# 9_h_bridge.net
KiCad netlist of a schematic drawn in Altium Designer
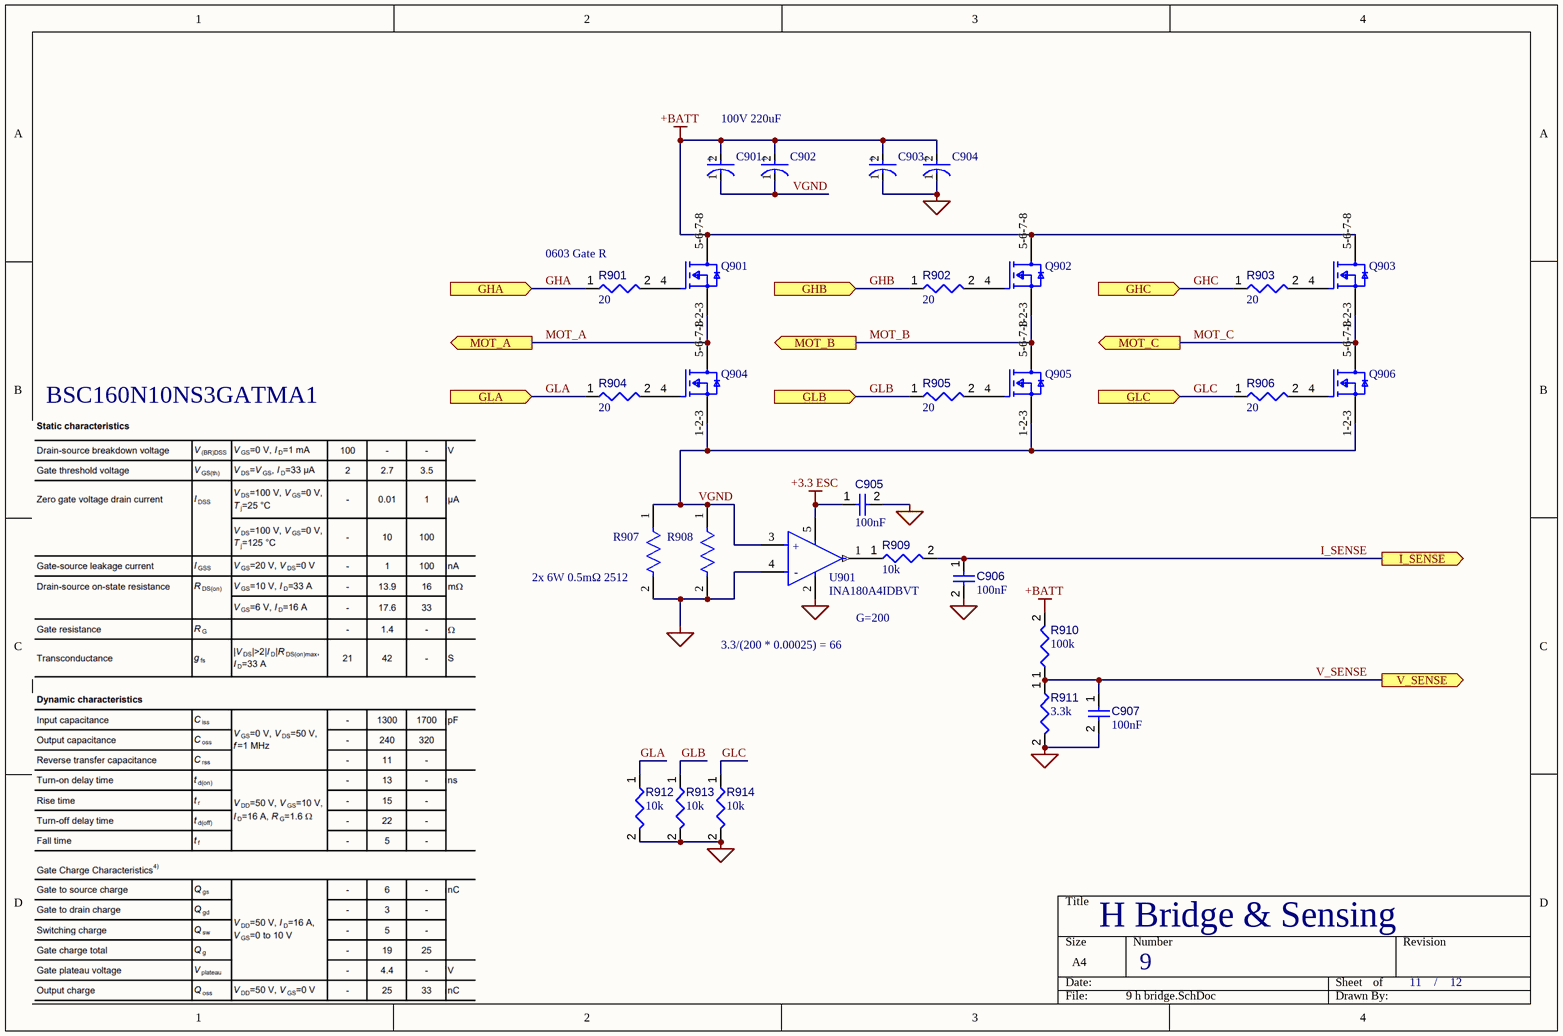
[diagram p0: 9 h bridge.SchDoc]

(export (version "E")
  (design (tool "Eeschema 10.0.6"))
  (components
    (comp (ref "C901")
      (value "EMVY101ARA101MKE0S")
      (footprint "FP-MVYAKE0-MFG")
      (description "CAP ALUM 100UF 20% 100V SMD")
      (fields (field (name "TOLERANCE") "20%"))
      (libsource (lib "Altium Content Vault") (part "203bc49f2ac43e59fd269a8c329ed05"))
    )
    (comp (ref "C902")
      (value "EMVY101ARA101MKE0S")
      (footprint "FP-MVYAKE0-MFG")
      (description "CAP ALUM 100UF 20% 100V SMD")
      (fields (field (name "TOLERANCE") "20%"))
      (libsource (lib "Altium Content Vault") (part "203bc49f2ac43e59fd269a8c329ed05"))
    )
    (comp (ref "C903")
      (value "EMVY101ARA101MKE0S")
      (footprint "FP-MVYAKE0-MFG")
      (description "CAP ALUM 100UF 20% 100V SMD")
      (fields (field (name "TOLERANCE") "20%"))
      (libsource (lib "Altium Content Vault") (part "203bc49f2ac43e59fd269a8c329ed05"))
    )
    (comp (ref "C904")
      (value "EMVY101ARA101MKE0S")
      (footprint "FP-MVYAKE0-MFG")
      (description "CAP ALUM 100UF 20% 100V SMD")
      (fields (field (name "TOLERANCE") "20%"))
      (libsource (lib "Altium Content Vault") (part "203bc49f2ac43e59fd269a8c329ed05"))
    )
    (comp (ref "C905")
      (value "100nF")
      (footprint "CAPC0402(1005)60_L")
      (description "Chip Capacitor, 100nF +/-20%, 25V, 0402, Thickness 0.6 mm")
      (fields (field (name "TOLERANCE") "10%") (field (name "Comment") "Capacitor 100nF +/-20% 25V 0402"))
      (libsource (lib "UBC Uncrewed Aircraft Systems") (part "CAP-NP-2"))
    )
    (comp (ref "C906")
      (value "100nF")
      (footprint "CAPC0402(1005)60_L")
      (description "Chip Capacitor, 100nF +/-20%, 25V, 0402, Thickness 0.6 mm")
      (fields (field (name "TOLERANCE") "10%") (field (name "Comment") "Capacitor 100nF +/-20% 25V 0402"))
      (libsource (lib "UBC Uncrewed Aircraft Systems") (part "CAP-NP-2"))
    )
    (comp (ref "C907")
      (value "100nF")
      (footprint "CAPC0402(1005)60_L")
      (description "Chip Capacitor, 100nF +/-20%, 25V, 0402, Thickness 0.6 mm")
      (fields (field (name "TOLERANCE") "10%") (field (name "Comment") "Capacitor 100nF +/-20% 25V 0402"))
      (libsource (lib "UBC Uncrewed Aircraft Systems") (part "CAP-NP-2"))
    )
    (comp (ref "Q901")
      (value "IAUC120N06S5N017ATMA1")
      (footprint "FP-PG-TDSON-8-MFG")
      (description "MOSFET N-CH 60V 120A TDSON-8-43")
      (libsource (lib "Altium Content Vault") (part "3085234d4498bcd04bc7e5400bb7c96"))
    )
    (comp (ref "Q902")
      (value "IAUC120N06S5N017ATMA1")
      (footprint "FP-PG-TDSON-8-MFG")
      (description "MOSFET N-CH 60V 120A TDSON-8-43")
      (libsource (lib "Altium Content Vault") (part "3085234d4498bcd04bc7e5400bb7c96"))
    )
    (comp (ref "Q903")
      (value "IAUC120N06S5N017ATMA1")
      (footprint "FP-PG-TDSON-8-MFG")
      (description "MOSFET N-CH 60V 120A TDSON-8-43")
      (libsource (lib "Altium Content Vault") (part "3085234d4498bcd04bc7e5400bb7c96"))
    )
    (comp (ref "Q904")
      (value "IAUC120N06S5N017ATMA1")
      (footprint "FP-PG-TDSON-8-MFG")
      (description "MOSFET N-CH 60V 120A TDSON-8-43")
      (libsource (lib "Altium Content Vault") (part "3085234d4498bcd04bc7e5400bb7c96"))
    )
    (comp (ref "Q905")
      (value "IAUC120N06S5N017ATMA1")
      (footprint "FP-PG-TDSON-8-MFG")
      (description "MOSFET N-CH 60V 120A TDSON-8-43")
      (libsource (lib "Altium Content Vault") (part "3085234d4498bcd04bc7e5400bb7c96"))
    )
    (comp (ref "Q906")
      (value "IAUC120N06S5N017ATMA1")
      (footprint "FP-PG-TDSON-8-MFG")
      (description "MOSFET N-CH 60V 120A TDSON-8-43")
      (libsource (lib "Altium Content Vault") (part "3085234d4498bcd04bc7e5400bb7c96"))
    )
    (comp (ref "R901")
      (value "20")
      (footprint "RESC0603(1608)_L")
      (description "Chip Resistor, 20 Ohms, +/-5 %, 0.1 W, -55 to 155 degC, 0603")
      (fields (field (name "TOLERANCE") "5%") (field (name "POWER") "100mW"))
      (libsource (lib "UBC Uncrewed Aircraft Systems") (part "RES-2"))
    )
    (comp (ref "R902")
      (value "20")
      (footprint "RESC0603(1608)_L")
      (description "Chip Resistor, 20 Ohms, +/-5 %, 0.1 W, -55 to 155 degC, 0603")
      (fields (field (name "TOLERANCE") "5%") (field (name "POWER") "100mW"))
      (libsource (lib "UBC Uncrewed Aircraft Systems") (part "RES-2"))
    )
    (comp (ref "R903")
      (value "20")
      (footprint "RESC0603(1608)_L")
      (description "Chip Resistor, 20 Ohms, +/-5 %, 0.1 W, -55 to 155 degC, 0603")
      (fields (field (name "TOLERANCE") "5%") (field (name "POWER") "100mW"))
      (libsource (lib "UBC Uncrewed Aircraft Systems") (part "RES-2"))
    )
    (comp (ref "R904")
      (value "20")
      (footprint "RESC0603(1608)_L")
      (description "Chip Resistor, 20 Ohms, +/-5 %, 0.1 W, -55 to 155 degC, 0603")
      (fields (field (name "TOLERANCE") "5%") (field (name "POWER") "100mW"))
      (libsource (lib "UBC Uncrewed Aircraft Systems") (part "RES-2"))
    )
    (comp (ref "R905")
      (value "20")
      (footprint "RESC0603(1608)_L")
      (description "Chip Resistor, 20 Ohms, +/-5 %, 0.1 W, -55 to 155 degC, 0603")
      (fields (field (name "TOLERANCE") "5%") (field (name "POWER") "100mW"))
      (libsource (lib "UBC Uncrewed Aircraft Systems") (part "RES-2"))
    )
    (comp (ref "R906")
      (value "20")
      (footprint "RESC0603(1608)_L")
      (description "Chip Resistor, 20 Ohms, +/-5 %, 0.1 W, -55 to 155 degC, 0603")
      (fields (field (name "TOLERANCE") "5%") (field (name "POWER") "100mW"))
      (libsource (lib "UBC Uncrewed Aircraft Systems") (part "RES-2"))
    )
    (comp (ref "R907")
      (value "PSL2NTEBL500F")
      (footprint "FP-PSL2NTEBL500F-MFG")
      (description "RES 500 UOHM 1% 8W NONSTANDARD")
      (libsource (lib "Altium Content Vault") (part "1029c3af85768c4190bb7ad29bc67b5"))
    )
    (comp (ref "R908")
      (value "PSL2NTEBL500F")
      (footprint "FP-PSL2NTEBL500F-MFG")
      (description "RES 500 UOHM 1% 8W NONSTANDARD")
      (libsource (lib "Altium Content Vault") (part "1029c3af85768c4190bb7ad29bc67b5"))
    )
    (comp (ref "R909")
      (value "10k")
      (footprint "RESC0402(1005)_L")
      (description "Chip Resistor, 10 kOhms, +/-1 %, 63 mW, -55 to 125 degC, 0402")
      (fields (field (name "POWER") "63mW") (field (name "TOLERANCE") "1%"))
      (libsource (lib "UBC Uncrewed Aircraft Systems") (part "RES-2"))
    )
    (comp (ref "R910")
      (value "100k")
      (footprint "RESC0402(1005)_L")
      (description "Chip Resistor, 100 kOhms, +/-1 %, 63 mW, -55 to 155 degC, 0402")
      (fields (field (name "TOLERANCE") "1%") (field (name "POWER") "63mW"))
      (libsource (lib "UBC Uncrewed Aircraft Systems") (part "RES-2"))
    )
    (comp (ref "R911")
      (value "3.3k")
      (footprint "RESC0402(1005)_L")
      (description "Chip Resistor, 3.3 kOhms, +/-1 %, 63 mW, -55 to 155 degC, 0402")
      (fields (field (name "TOLERANCE") "1%") (field (name "POWER") "63mW"))
      (libsource (lib "UBC Uncrewed Aircraft Systems") (part "RES-2"))
    )
    (comp (ref "R912")
      (value "10k")
      (footprint "RESC0402(1005)_L")
      (description "Chip Resistor, 10 kOhms, +/-1 %, 63 mW, -55 to 125 degC, 0402")
      (fields (field (name "POWER") "63mW") (field (name "TOLERANCE") "1%"))
      (libsource (lib "UBC Uncrewed Aircraft Systems") (part "RES-2"))
    )
    (comp (ref "R913")
      (value "10k")
      (footprint "RESC0402(1005)_L")
      (description "Chip Resistor, 10 kOhms, +/-1 %, 63 mW, -55 to 125 degC, 0402")
      (fields (field (name "POWER") "63mW") (field (name "TOLERANCE") "1%"))
      (libsource (lib "UBC Uncrewed Aircraft Systems") (part "RES-2"))
    )
    (comp (ref "R914")
      (value "10k")
      (footprint "RESC0402(1005)_L")
      (description "Chip Resistor, 10 kOhms, +/-1 %, 63 mW, -55 to 125 degC, 0402")
      (fields (field (name "POWER") "63mW") (field (name "TOLERANCE") "1%"))
      (libsource (lib "UBC Uncrewed Aircraft Systems") (part "RES-2"))
    )
    (comp (ref "U901")
      (value "INA180A4IDBVT")
      (footprint "FP-DBV0005A-MFG")
      (description "IC CURR SENSE 1 CIRCUIT SOT23-5")
      (fields
        (field (name "OCTOPART") "https://octopart.com/ina180a4idbvt-texas+instruments-81856280")
        (field (name "MANUFACTURER") "Texas Instruments")
      )
      (libsource (lib "Altium Content Vault") (part "0a55cf1a948ad01a3239aec1b7efad0"))
    )
  )
  (nets
    (net (code "1") (name "+3.3 ESC") (class "Default")
      (node (ref "C905") (pin "1") (pinfunction "1_1") (pintype "passive"))
      (node (ref "U901") (pin "5") (pinfunction "VS_5") (pintype "power_in"))
    )
    (net (code "2") (name "+BATT") (class "Default")
      (node (ref "C901") (pin "2") (pinfunction "A_2") (pintype "passive"))
      (node (ref "C902") (pin "2") (pinfunction "A_2") (pintype "passive"))
      (node (ref "C903") (pin "2") (pinfunction "A_2") (pintype "passive"))
      (node (ref "C904") (pin "2") (pinfunction "A_2") (pintype "passive"))
      (node (ref "Q901") (pin "5-6-7-8") (pinfunction "D_5-6-7-8") (pintype "passive"))
      (node (ref "Q902") (pin "5-6-7-8") (pinfunction "D_5-6-7-8") (pintype "passive"))
      (node (ref "Q903") (pin "5-6-7-8") (pinfunction "D_5-6-7-8") (pintype "passive"))
      (node (ref "R910") (pin "2") (pinfunction "2_2") (pintype "passive"))
    )
    (net (code "3") (name "/GHA") (class "Default")
      (node (ref "R901") (pin "1") (pinfunction "1_1") (pintype "passive"))
    )
    (net (code "4") (name "/GHB") (class "Default")
      (node (ref "R902") (pin "1") (pinfunction "1_1") (pintype "passive"))
    )
    (net (code "5") (name "/GHC") (class "Default")
      (node (ref "R903") (pin "1") (pinfunction "1_1") (pintype "passive"))
    )
    (net (code "6") (name "/GLA") (class "Default")
      (node (ref "R904") (pin "1") (pinfunction "1_1") (pintype "passive"))
      (node (ref "R912") (pin "1") (pinfunction "1_1") (pintype "passive"))
    )
    (net (code "7") (name "/GLB") (class "Default")
      (node (ref "R905") (pin "1") (pinfunction "1_1") (pintype "passive"))
      (node (ref "R913") (pin "1") (pinfunction "1_1") (pintype "passive"))
    )
    (net (code "8") (name "/GLC") (class "Default")
      (node (ref "R906") (pin "1") (pinfunction "1_1") (pintype "passive"))
      (node (ref "R914") (pin "1") (pinfunction "1_1") (pintype "passive"))
    )
    (net (code "9") (name "/I_SENSE") (class "Default")
      (node (ref "C906") (pin "1") (pinfunction "1_1") (pintype "passive"))
      (node (ref "R909") (pin "2") (pinfunction "2_2") (pintype "passive"))
    )
    (net (code "10") (name "/MOT_A") (class "Default")
      (node (ref "Q901") (pin "1-2-3") (pinfunction "S_1-2-3") (pintype "passive"))
      (node (ref "Q904") (pin "5-6-7-8") (pinfunction "D_5-6-7-8") (pintype "passive"))
    )
    (net (code "11") (name "/MOT_B") (class "Default")
      (node (ref "Q902") (pin "1-2-3") (pinfunction "S_1-2-3") (pintype "passive"))
      (node (ref "Q905") (pin "5-6-7-8") (pinfunction "D_5-6-7-8") (pintype "passive"))
    )
    (net (code "12") (name "/MOT_C") (class "Default")
      (node (ref "Q903") (pin "1-2-3") (pinfunction "S_1-2-3") (pintype "passive"))
      (node (ref "Q906") (pin "5-6-7-8") (pinfunction "D_5-6-7-8") (pintype "passive"))
    )
    (net (code "13") (name "/VGND") (class "Default")
      (node (ref "C901") (pin "1") (pinfunction "C_1") (pintype "passive"))
      (node (ref "C902") (pin "1") (pinfunction "C_1") (pintype "passive"))
      (node (ref "Q904") (pin "1-2-3") (pinfunction "S_1-2-3") (pintype "passive"))
      (node (ref "Q905") (pin "1-2-3") (pinfunction "S_1-2-3") (pintype "passive"))
      (node (ref "Q906") (pin "1-2-3") (pinfunction "S_1-2-3") (pintype "passive"))
      (node (ref "R907") (pin "1") (pinfunction "1_1") (pintype "passive"))
      (node (ref "R908") (pin "1") (pinfunction "1_1") (pintype "passive"))
      (node (ref "U901") (pin "3") (pinfunction "IN+_3") (pintype "tri_state"))
    )
    (net (code "14") (name "/V_SENSE") (class "Default")
      (node (ref "C907") (pin "1") (pinfunction "1_1") (pintype "passive"))
      (node (ref "R910") (pin "1") (pinfunction "1_1") (pintype "passive"))
      (node (ref "R911") (pin "1") (pinfunction "1_1") (pintype "passive"))
    )
    (net (code "15") (name "Net-(Q901-G)") (class "Default")
      (node (ref "Q901") (pin "4") (pinfunction "G_4") (pintype "passive"))
      (node (ref "R901") (pin "2") (pinfunction "2_2") (pintype "passive"))
    )
    (net (code "16") (name "Net-(Q902-G)") (class "Default")
      (node (ref "Q902") (pin "4") (pinfunction "G_4") (pintype "passive"))
      (node (ref "R902") (pin "2") (pinfunction "2_2") (pintype "passive"))
    )
    (net (code "17") (name "Net-(Q903-G)") (class "Default")
      (node (ref "Q903") (pin "4") (pinfunction "G_4") (pintype "passive"))
      (node (ref "R903") (pin "2") (pinfunction "2_2") (pintype "passive"))
    )
    (net (code "18") (name "Net-(Q904-G)") (class "Default")
      (node (ref "Q904") (pin "4") (pinfunction "G_4") (pintype "passive"))
      (node (ref "R904") (pin "2") (pinfunction "2_2") (pintype "passive"))
    )
    (net (code "19") (name "Net-(Q905-G)") (class "Default")
      (node (ref "Q905") (pin "4") (pinfunction "G_4") (pintype "passive"))
      (node (ref "R905") (pin "2") (pinfunction "2_2") (pintype "passive"))
    )
    (net (code "20") (name "Net-(Q906-G)") (class "Default")
      (node (ref "Q906") (pin "4") (pinfunction "G_4") (pintype "passive"))
      (node (ref "R906") (pin "2") (pinfunction "2_2") (pintype "passive"))
    )
    (net (code "21") (name "Net-(U901-OUT)") (class "Default")
      (node (ref "R909") (pin "1") (pinfunction "1_1") (pintype "passive"))
      (node (ref "U901") (pin "1") (pinfunction "OUT_1") (pintype "output"))
    )
    (net (code "22") (name "PGND") (class "Default")
      (node (ref "C903") (pin "1") (pinfunction "C_1") (pintype "passive"))
      (node (ref "C904") (pin "1") (pinfunction "C_1") (pintype "passive"))
      (node (ref "C905") (pin "2") (pinfunction "2_2") (pintype "passive"))
      (node (ref "C906") (pin "2") (pinfunction "2_2") (pintype "passive"))
      (node (ref "C907") (pin "2") (pinfunction "2_2") (pintype "passive"))
      (node (ref "R907") (pin "2") (pinfunction "2_2") (pintype "passive"))
      (node (ref "R908") (pin "2") (pinfunction "2_2") (pintype "passive"))
      (node (ref "R911") (pin "2") (pinfunction "2_2") (pintype "passive"))
      (node (ref "R912") (pin "2") (pinfunction "2_2") (pintype "passive"))
      (node (ref "R913") (pin "2") (pinfunction "2_2") (pintype "passive"))
      (node (ref "R914") (pin "2") (pinfunction "2_2") (pintype "passive"))
      (node (ref "U901") (pin "2") (pinfunction "GND_2") (pintype "power_in"))
      (node (ref "U901") (pin "4") (pinfunction "IN-_4") (pintype "tri_state"))
    )
  )
)
